# PWR.net
KiCad netlist of a schematic drawn in Altium Designer
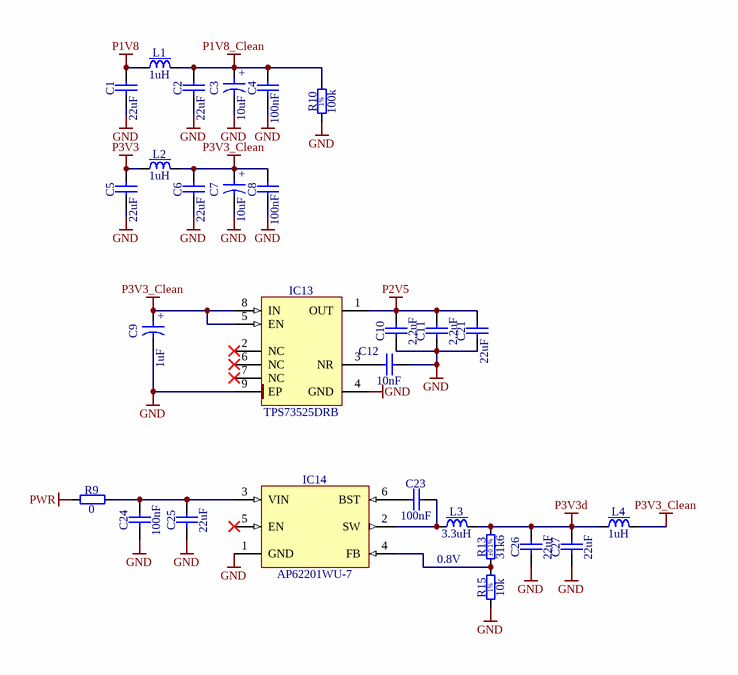
[diagram p0: PWR.SchDoc]

(export (version "E")
  (design (tool "Eeschema 10.0.6"))
  (components
    (comp (ref "C1")
      (value "22uF")
      (footprint "CAPC2012X135N")
      (description "Non-polarised capacitor")
      (fields
        (field (name "PART NUMBER") "CC0805_22UF_16V_10%_X5R")
        (field (name "VOLTAGE") "16V")
        (field (name "AUTHOR") "CERN DEM JLC")
      )
      (libsource (lib "Capacitors") (part "Capacitor - non polarized"))
    )
    (comp (ref "C2")
      (value "22uF")
      (footprint "CAPC2012X135N")
      (description "Non-polarised capacitor")
      (fields
        (field (name "PART NUMBER") "CC0805_22UF_16V_10%_X5R")
        (field (name "VOLTAGE") "16V")
        (field (name "AUTHOR") "CERN DEM JLC")
      )
      (libsource (lib "Capacitors") (part "Capacitor - non polarized"))
    )
    (comp (ref "C3")
      (value "10uF")
      (footprint "CAPMP3216X180N")
      (description "Polarised capacitor")
      (fields
        (field (name "PART NUMBER") "CTE3216-18_10UF_16V_20%_AVX_TCJ")
        (field (name "VOLTAGE") "16V")
        (field (name "AUTHOR") "CERN DEM JLC")
      )
      (libsource (lib "Capacitors") (part "Capacitor - polarized"))
    )
    (comp (ref "C4")
      (value "100nF")
      (footprint "CAPC1005X55N")
      (description "Non-polarised capacitor")
      (fields
        (field (name "PART NUMBER") "CC0402_100NF_50V_10%_X7R")
        (field (name "VOLTAGE") "50V")
        (field (name "AUTHOR") "CERN DEM MR")
      )
      (libsource (lib "Capacitors") (part "Capacitor - non polarized"))
    )
    (comp (ref "C5")
      (value "22uF")
      (footprint "CAPC2012X135N")
      (description "Non-polarised capacitor")
      (fields
        (field (name "PART NUMBER") "CC0805_22UF_16V_10%_X5R")
        (field (name "VOLTAGE") "16V")
        (field (name "AUTHOR") "CERN DEM JLC")
      )
      (libsource (lib "Capacitors") (part "Capacitor - non polarized"))
    )
    (comp (ref "C6")
      (value "22uF")
      (footprint "CAPC2012X135N")
      (description "Non-polarised capacitor")
      (fields
        (field (name "PART NUMBER") "CC0805_22UF_16V_10%_X5R")
        (field (name "VOLTAGE") "16V")
        (field (name "AUTHOR") "CERN DEM JLC")
      )
      (libsource (lib "Capacitors") (part "Capacitor - non polarized"))
    )
    (comp (ref "C7")
      (value "10uF")
      (footprint "CAPMP3216X180N")
      (description "Polarised capacitor")
      (fields
        (field (name "PART NUMBER") "CTE3216-18_10UF_16V_20%_AVX_TCJ")
        (field (name "VOLTAGE") "16V")
        (field (name "AUTHOR") "CERN DEM JLC")
      )
      (libsource (lib "Capacitors") (part "Capacitor - polarized"))
    )
    (comp (ref "C8")
      (value "100nF")
      (footprint "CAPC1005X55N")
      (description "Non-polarised capacitor")
      (fields
        (field (name "PART NUMBER") "CC0402_100NF_50V_10%_X7R")
        (field (name "VOLTAGE") "50V")
        (field (name "AUTHOR") "CERN DEM MR")
      )
      (libsource (lib "Capacitors") (part "Capacitor - non polarized"))
    )
    (comp (ref "C9")
      (value "1uF")
      (footprint "CAPMP3216X180N")
      (description "Polarised capacitor")
      (fields
        (field (name "PART NUMBER") "CTE3216-18_1UF_16V_10%")
        (field (name "VOLTAGE") "16V")
        (field (name "AUTHOR") "CERN DEM JLC")
      )
      (libsource (lib "Capacitors") (part "Capacitor - polarized"))
    )
    (comp (ref "C10")
      (value "2.2uF")
      (footprint "CAPC1608X87N")
      (description "Non-polarised capacitor")
      (fields
        (field (name "PART NUMBER") "CC0603_2.2UF_16V_10%_X5R")
        (field (name "VOLTAGE") "16V")
        (field (name "AUTHOR") "CERN DEM JLC")
      )
      (libsource (lib "Capacitors") (part "Capacitor - non polarized"))
    )
    (comp (ref "C11")
      (value "2.2uF")
      (footprint "CAPC1608X87N")
      (description "Non-polarised capacitor")
      (fields
        (field (name "PART NUMBER") "CC0603_2.2UF_16V_10%_X5R")
        (field (name "VOLTAGE") "16V")
        (field (name "AUTHOR") "CERN DEM JLC")
      )
      (libsource (lib "Capacitors") (part "Capacitor - non polarized"))
    )
    (comp (ref "C12")
      (value "10nF")
      (footprint "CAPC1005X55N")
      (description "Non-polarised capacitor")
      (fields
        (field (name "PART NUMBER") "CC0402_10NF_16V_10%_X7R")
        (field (name "VOLTAGE") "16V")
        (field (name "AUTHOR") "CERN DEM JLC")
      )
      (libsource (lib "Capacitors") (part "Capacitor - non polarized"))
    )
    (comp (ref "C21")
      (value "22uF")
      (footprint "CAPC2012X135N")
      (description "Non-polarised capacitor")
      (fields
        (field (name "PART NUMBER") "CC0805_22UF_16V_10%_X5R")
        (field (name "VOLTAGE") "16V")
        (field (name "AUTHOR") "CERN DEM JLC")
      )
      (libsource (lib "Capacitors") (part "Capacitor - non polarized"))
    )
    (comp (ref "C23")
      (value "100nF")
      (footprint "CAPC1005X55N")
      (description "Non-polarised capacitor")
      (fields
        (field (name "PART NUMBER") "CC0402_100NF_16V_10%_X5R")
        (field (name "VOLTAGE") "16V")
        (field (name "AUTHOR") "CERN DEM JLC")
      )
      (libsource (lib "Capacitors") (part "Capacitor - non polarized"))
    )
    (comp (ref "C24")
      (value "100nF")
      (footprint "CAPC1005X55N")
      (description "Non-polarised capacitor")
      (fields
        (field (name "PART NUMBER") "CC0402_100NF_16V_10%_X5R")
        (field (name "VOLTAGE") "16V")
        (field (name "AUTHOR") "CERN DEM JLC")
      )
      (libsource (lib "Capacitors") (part "Capacitor - non polarized"))
    )
    (comp (ref "C25")
      (value "22uF")
      (footprint "CAPC2012X135N")
      (description "Non-polarised capacitor")
      (fields
        (field (name "PART NUMBER") "CC0805_22UF_16V_10%_X5R")
        (field (name "VOLTAGE") "16V")
        (field (name "AUTHOR") "CERN DEM JLC")
      )
      (libsource (lib "Capacitors") (part "Capacitor - non polarized"))
    )
    (comp (ref "C26")
      (value "22uF")
      (footprint "CAPC2012X135N")
      (description "Non-polarised capacitor")
      (fields
        (field (name "PART NUMBER") "CC0805_22UF_16V_10%_X5R")
        (field (name "VOLTAGE") "16V")
        (field (name "AUTHOR") "CERN DEM JLC")
      )
      (libsource (lib "Capacitors") (part "Capacitor - non polarized"))
    )
    (comp (ref "C27")
      (value "22uF")
      (footprint "CAPC2012X135N")
      (description "Non-polarised capacitor")
      (fields
        (field (name "PART NUMBER") "CC0805_22UF_16V_10%_X5R")
        (field (name "VOLTAGE") "16V")
        (field (name "AUTHOR") "CERN DEM JLC")
      )
      (libsource (lib "Capacitors") (part "Capacitor - non polarized"))
    )
    (comp (ref "IC13")
      (value "TPS73525DRB")
      (footprint "TEXAS_DRB(S-PVSON-N8)")
      (description "500mA, Low Quiescent Current, Low Noise, High PSRR, Low-Dropout Linear Regulator")
      (fields (field (name "MANUFACTURER") "TEXAS INSTRUMENTS") (field (name "AUTHOR") "CERN DEM BC"))
      (libsource (lib "ICs And Semiconductors") (part "TPS735xxDRB"))
    )
    (comp (ref "IC14")
      (value "AP62201WU-7")
      (footprint "SOT95P280X100-6N")
      (description "4.2V TO 18V INPUT, 2A LOW IQ SYNCHRONOUS BUCK CONVERTER")
      (fields
        (field (name "MANUFACTURER") "DIODES INCORPORATED")
        (field (name "MANUFACTURER PART NUMBER") "AP62201WU")
        (field (name "AUTHOR") "CERN DEM HF")
      )
      (libsource (lib "ICs And Semiconductors") (part "AP62201WU"))
    )
    (comp (ref "L1")
      (value "1uH")
      (footprint "IND_PANASONIC_ELLVGG")
      (description "Inductor With Core")
      (fields
        (field (name "PART NUMBER") "IND_1UH_30%_PANASONIC_ELLVGG1R0N")
        (field (name "POWER") "1.8A")
        (field (name "AUTHOR") "CERN DEM JLC")
      )
      (libsource (lib "Inductors & Transformers") (part "Inductor With Magnetic core"))
    )
    (comp (ref "L2")
      (value "1uH")
      (footprint "IND_PANASONIC_ELLVGG")
      (description "Inductor With Core")
      (fields
        (field (name "PART NUMBER") "IND_1UH_30%_PANASONIC_ELLVGG1R0N")
        (field (name "POWER") "1.8A")
        (field (name "AUTHOR") "CERN DEM JLC")
      )
      (libsource (lib "Inductors & Transformers") (part "Inductor With Magnetic core"))
    )
    (comp (ref "L3")
      (value "3.3uH")
      (footprint "IND_WURTH_WE-TPC_4828")
      (description "Inductor With Core")
      (fields
        (field (name "PART NUMBER") "IND_3.3UH_30%_WURTH_WE-TPC_744043003")
        (field (name "POWER") "2.15A")
        (field (name "AUTHOR") "CERN DEM JLC")
      )
      (libsource (lib "Inductors & Transformers") (part "Inductor With Magnetic core"))
    )
    (comp (ref "L4")
      (value "1uH")
      (footprint "IND_PANASONIC_ELLVGG")
      (description "Inductor With Core")
      (fields
        (field (name "PART NUMBER") "IND_1UH_30%_PANASONIC_ELLVGG1R0N")
        (field (name "POWER") "1.8A")
        (field (name "AUTHOR") "CERN DEM JLC")
      )
      (libsource (lib "Inductors & Transformers") (part "Inductor With Magnetic core"))
    )
    (comp (ref "R9")
      (value "0")
      (footprint "RESC1608X55N")
      (description "Resistor")
      (fields
        (field (name "PART NUMBER") "R0603_0R_JUMPER")
        (field (name "MANUFACTURER") "GENERIC")
        (field (name "AUTHOR") "CERN DEM JLC")
      )
      (libsource (lib "Resistors") (part "Resistor"))
    )
    (comp (ref "R10")
      (value "100k")
      (footprint "RESC1005X40N")
      (description "Resistor - 1%")
      (fields
        (field (name "PART NUMBER") "R0402_100K_1%_0.0625W_100PPM")
        (field (name "POWER") "0.0625W")
        (field (name "AUTHOR") "CERN DEM JLC")
      )
      (libsource (lib "Resistors") (part "Resistor - 1%"))
    )
    (comp (ref "R13")
      (value "31k6")
      (footprint "RESC1005X35N")
      (description "Resistor - 0.1%")
      (fields
        (field (name "TOLERANCE") "±0.1%")
        (field (name "PART NUMBER") "R0402_31K6_0.1%_0.063W_25PPM_YAGEO_RT")
        (field (name "POWER") "0.063W")
        (field (name "AUTHOR") "CERN DEM BC")
      )
      (libsource (lib "Resistors") (part "Resistor - 0.1%"))
    )
    (comp (ref "R15")
      (value "10k")
      (footprint "RESC1005X40N")
      (description "Resistor - 1%")
      (fields
        (field (name "PART NUMBER") "R0402_10K_1%_0.0625W_100PPM")
        (field (name "POWER") "0.0625W")
        (field (name "AUTHOR") "CERN DEM JLC")
      )
      (libsource (lib "Resistors") (part "Resistor - 1%"))
    )
  )
  (nets
    (net (code "1") (name "GND") (class "Default")
      (node (ref "C1") (pin "1") (pinfunction "1_1") (pintype "passive"))
      (node (ref "C10") (pin "1") (pinfunction "1_1") (pintype "passive"))
      (node (ref "C11") (pin "1") (pinfunction "1_1") (pintype "passive"))
      (node (ref "C12") (pin "2") (pinfunction "2_2") (pintype "passive"))
      (node (ref "C2") (pin "1") (pinfunction "1_1") (pintype "passive"))
      (node (ref "C21") (pin "1") (pinfunction "1_1") (pintype "passive"))
      (node (ref "C24") (pin "1") (pinfunction "1_1") (pintype "passive"))
      (node (ref "C25") (pin "1") (pinfunction "1_1") (pintype "passive"))
      (node (ref "C26") (pin "1") (pinfunction "1_1") (pintype "passive"))
      (node (ref "C27") (pin "1") (pinfunction "1_1") (pintype "passive"))
      (node (ref "C3") (pin "2") (pinfunction "2_2") (pintype "passive"))
      (node (ref "C4") (pin "1") (pinfunction "1_1") (pintype "passive"))
      (node (ref "C5") (pin "1") (pinfunction "1_1") (pintype "passive"))
      (node (ref "C6") (pin "1") (pinfunction "1_1") (pintype "passive"))
      (node (ref "C7") (pin "2") (pinfunction "2_2") (pintype "passive"))
      (node (ref "C8") (pin "1") (pinfunction "1_1") (pintype "passive"))
      (node (ref "C9") (pin "2") (pinfunction "2_2") (pintype "passive"))
      (node (ref "IC13") (pin "4") (pinfunction "GND_4") (pintype "power_in"))
      (node (ref "IC13") (pin "9") (pinfunction "EP_9") (pintype "power_in"))
      (node (ref "IC14") (pin "1") (pinfunction "GND_1") (pintype "power_in"))
      (node (ref "R10") (pin "1") (pinfunction "1_1") (pintype "passive"))
      (node (ref "R15") (pin "1") (pinfunction "1_1") (pintype "passive"))
    )
    (net (code "2") (name "Net-(IC13-NR)") (class "Default")
      (node (ref "C12") (pin "1") (pinfunction "1_1") (pintype "passive"))
      (node (ref "IC13") (pin "3") (pinfunction "NR_3") (pintype "passive"))
    )
    (net (code "3") (name "Net-(IC14-BST)") (class "Default")
      (node (ref "C23") (pin "1") (pinfunction "1_1") (pintype "passive"))
      (node (ref "IC14") (pin "6") (pinfunction "BST_6") (pintype "input"))
    )
    (net (code "4") (name "Net-(IC14-FB)") (class "Default")
      (node (ref "IC14") (pin "4") (pinfunction "FB_4") (pintype "input"))
      (node (ref "R13") (pin "1") (pinfunction "1_1") (pintype "passive"))
      (node (ref "R15") (pin "2") (pinfunction "2_2") (pintype "passive"))
    )
    (net (code "5") (name "Net-(IC14-SW)") (class "Default")
      (node (ref "C23") (pin "2") (pinfunction "2_2") (pintype "passive"))
      (node (ref "IC14") (pin "2") (pinfunction "SW_2") (pintype "output"))
      (node (ref "L3") (pin "1") (pinfunction "1_1") (pintype "passive"))
    )
    (net (code "6") (name "Net-(IC14-VIN)") (class "Default")
      (node (ref "C24") (pin "2") (pinfunction "2_2") (pintype "passive"))
      (node (ref "C25") (pin "2") (pinfunction "2_2") (pintype "passive"))
      (node (ref "IC14") (pin "3") (pinfunction "VIN_3") (pintype "input"))
      (node (ref "R9") (pin "2") (pinfunction "2_2") (pintype "passive"))
    )
    (net (code "7") (name "P1V8") (class "Default")
      (node (ref "C1") (pin "2") (pinfunction "2_2") (pintype "passive"))
      (node (ref "L1") (pin "1") (pinfunction "1_1") (pintype "passive"))
    )
    (net (code "8") (name "P1V8_Clean") (class "Default")
      (node (ref "C2") (pin "2") (pinfunction "2_2") (pintype "passive"))
      (node (ref "C3") (pin "1") (pinfunction "1_1") (pintype "passive"))
      (node (ref "C4") (pin "2") (pinfunction "2_2") (pintype "passive"))
      (node (ref "L1") (pin "2") (pinfunction "2_2") (pintype "passive"))
      (node (ref "R10") (pin "2") (pinfunction "2_2") (pintype "passive"))
    )
    (net (code "9") (name "P2V5") (class "Default")
      (node (ref "C10") (pin "2") (pinfunction "2_2") (pintype "passive"))
      (node (ref "C11") (pin "2") (pinfunction "2_2") (pintype "passive"))
      (node (ref "C21") (pin "2") (pinfunction "2_2") (pintype "passive"))
      (node (ref "IC13") (pin "1") (pinfunction "OUT_1") (pintype "power_in"))
    )
    (net (code "10") (name "P3V3") (class "Default")
      (node (ref "C5") (pin "2") (pinfunction "2_2") (pintype "passive"))
      (node (ref "L2") (pin "1") (pinfunction "1_1") (pintype "passive"))
    )
    (net (code "11") (name "P3V3_Clean") (class "Default")
      (node (ref "C6") (pin "2") (pinfunction "2_2") (pintype "passive"))
      (node (ref "C7") (pin "1") (pinfunction "1_1") (pintype "passive"))
      (node (ref "C8") (pin "2") (pinfunction "2_2") (pintype "passive"))
      (node (ref "C9") (pin "1") (pinfunction "1_1") (pintype "passive"))
      (node (ref "IC13") (pin "5") (pinfunction "EN_5") (pintype "input"))
      (node (ref "IC13") (pin "8") (pinfunction "IN_8") (pintype "input"))
      (node (ref "L2") (pin "2") (pinfunction "2_2") (pintype "passive"))
      (node (ref "L4") (pin "2") (pinfunction "2_2") (pintype "passive"))
    )
    (net (code "12") (name "P3V3d") (class "Default")
      (node (ref "C26") (pin "2") (pinfunction "2_2") (pintype "passive"))
      (node (ref "C27") (pin "2") (pinfunction "2_2") (pintype "passive"))
      (node (ref "L3") (pin "2") (pinfunction "2_2") (pintype "passive"))
      (node (ref "L4") (pin "1") (pinfunction "1_1") (pintype "passive"))
      (node (ref "R13") (pin "2") (pinfunction "2_2") (pintype "passive"))
    )
    (net (code "13") (name "PWR") (class "Default")
      (node (ref "R9") (pin "1") (pinfunction "1_1") (pintype "passive"))
    )
    (net (code "14") (name "unconnected-(IC13-NC-Pad2)") (class "Default")
      (node (ref "IC13") (pin "2") (pinfunction "NC_2") (pintype "passive+no_connect"))
    )
    (net (code "15") (name "unconnected-(IC13-NC-Pad6)") (class "Default")
      (node (ref "IC13") (pin "6") (pinfunction "NC_6") (pintype "passive+no_connect"))
    )
    (net (code "16") (name "unconnected-(IC13-NC-Pad7)") (class "Default")
      (node (ref "IC13") (pin "7") (pinfunction "NC_7") (pintype "passive+no_connect"))
    )
    (net (code "17") (name "unconnected-(IC14-EN-Pad5)") (class "Default")
      (node (ref "IC14") (pin "5") (pinfunction "EN_5") (pintype "input+no_connect"))
    )
  )
)
